# AttoDD.net
KiCad netlist of a schematic drawn in Altium Designer
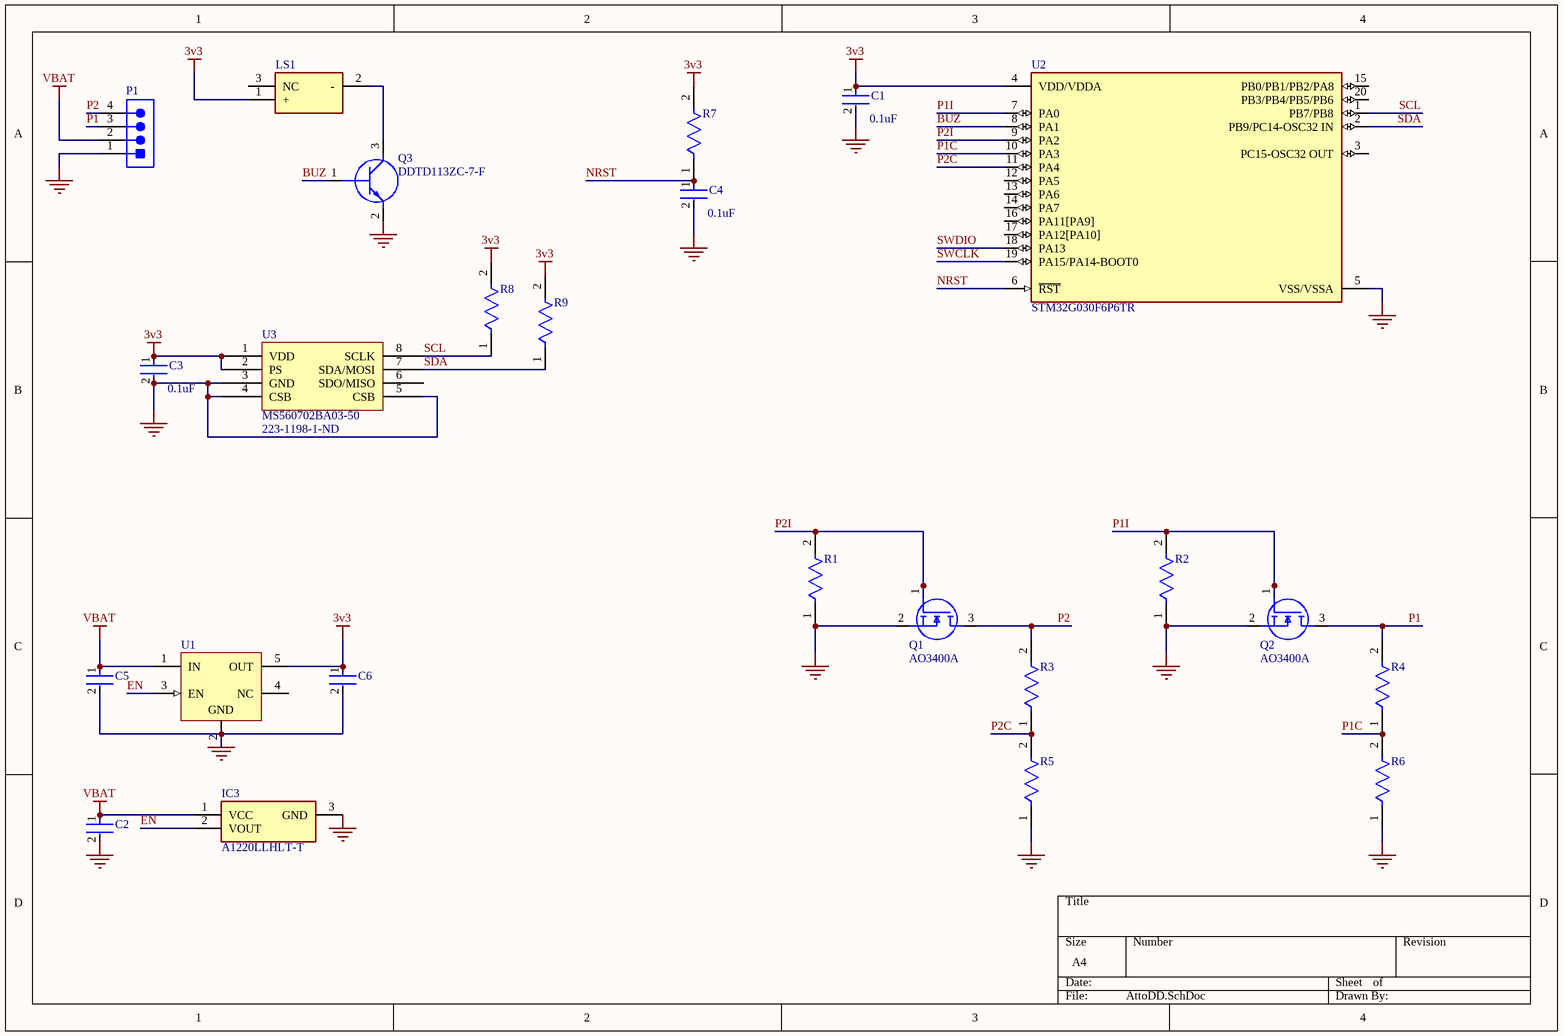
[diagram p0: AttoDD.SchDoc]

(export (version "E")
  (design (tool "Eeschema 10.0.6"))
  (components
    (comp (ref "C1")
      (value "0.1uF")
      (footprint "FP-C0402-BB-MFG")
      (description "CAP CER 0.1UF 10V X5R 0402")
      (fields (field (name "MANUFACTURER") "Kemet") (field (name "TOLERANCE") "0.1"))
      (libsource (lib "Altium Content Vault") (part "b4654b650e69147ec39a6b967a45e02"))
    )
    (comp (ref "C2")
      (value "C0402C105K8PACTU")
      (footprint "FP-C0402C105K8PACTU-MFG")
      (description "CAP CER 1UF 10V X5R 0402")
      (fields (field (name "VOLTAGE") "10V") (field (name "TOLERANCE") "10%"))
      (libsource (lib "Altium Content Vault") (part "11868f565c42a9108669ba33697ecf6"))
    )
    (comp (ref "C3")
      (value "0.1uF")
      (footprint "FP-C0402-BB-MFG")
      (description "CAP CER 0.1UF 10V X5R 0402")
      (fields (field (name "MANUFACTURER") "Kemet") (field (name "TOLERANCE") "0.1"))
      (libsource (lib "Altium Content Vault") (part "b4654b650e69147ec39a6b967a45e02"))
    )
    (comp (ref "C4")
      (value "0.1uF")
      (footprint "FP-C0402-BB-MFG")
      (description "CAP CER 0.1UF 10V X5R 0402")
      (fields (field (name "MANUFACTURER") "Kemet") (field (name "TOLERANCE") "0.1"))
      (libsource (lib "Altium Content Vault") (part "b4654b650e69147ec39a6b967a45e02"))
    )
    (comp (ref "C5")
      (value "C0402C105K8PACTU")
      (footprint "FP-C0402C105K8PACTU-MFG")
      (description "CAP CER 1UF 10V X5R 0402")
      (fields (field (name "VOLTAGE") "10V") (field (name "TOLERANCE") "10%"))
      (libsource (lib "Altium Content Vault") (part "11868f565c42a9108669ba33697ecf6"))
    )
    (comp (ref "C6")
      (value "C0402C105K8PACTU")
      (footprint "FP-C0402C105K8PACTU-MFG")
      (description "CAP CER 1UF 10V X5R 0402")
      (fields (field (name "VOLTAGE") "10V") (field (name "TOLERANCE") "10%"))
      (libsource (lib "Altium Content Vault") (part "11868f565c42a9108669ba33697ecf6"))
    )
    (comp (ref "IC3")
      (value "A1220LLHLT-T")
      (footprint "SamacSys:A3213ELHLTT")
      (description "Integrated Circuit")
      (libsource (lib "*") (part "A1220LLHLT-T"))
    )
    (comp (ref "LS1")
      (value "CMT-0525-75-SMT-TR")
      (footprint "SamacSys:CMT052575SMTTR")
      (description "Loudspeaker or Buzzer")
      (libsource (lib "*") (part "CMT-0525-75-SMT-TR"))
    )
    (comp (ref "P1")
      (value "GRPB041VWVN-RC")
      (footprint "SLIN-GRPB041VWVN-RC_V")
      (fields (field (name "MANUFACTURER") "Sullins"))
      (libsource (lib "Altium Content Vault") (part "CN-1P-M-R4"))
    )
    (comp (ref "Q1")
      (value "AO3400A")
      (footprint "SamacSys:SOT95P280X125-3N")
      (description "MOSFET (N-Channel)")
      (libsource (lib "*") (part "AO3400A"))
    )
    (comp (ref "Q2")
      (value "AO3400A")
      (footprint "SamacSys:SOT95P280X125-3N")
      (description "MOSFET (N-Channel)")
      (libsource (lib "*") (part "AO3400A"))
    )
    (comp (ref "Q3")
      (value "DDTD113ZC-7-F")
      (footprint "SamacSys:SOT96P240X110-3N")
      (description "Transistor BJT NPN")
      (libsource (lib "*") (part "DDTD113ZC-7-F"))
    )
    (comp (ref "R1")
      (value "CRCW0402100KFKED")
      (footprint "FP-CRCW0402-e3-IPC_C")
      (description "RES Thick Film, 100kΩ, 1%, 0.063W, 100ppm/°C, 0402")
      (fields (field (name "TOLERANCE") "1%"))
      (libsource (lib "Altium Content Vault") (part "1029c3af85768c4190bb7ad29bc67b5"))
    )
    (comp (ref "R2")
      (value "CRCW0402100KFKED")
      (footprint "FP-CRCW0402-e3-IPC_C")
      (description "RES Thick Film, 100kΩ, 1%, 0.063W, 100ppm/°C, 0402")
      (fields (field (name "TOLERANCE") "1%"))
      (libsource (lib "Altium Content Vault") (part "1029c3af85768c4190bb7ad29bc67b5"))
    )
    (comp (ref "R3")
      (value "CRCW0402100KFKED")
      (footprint "FP-CRCW0402-e3-IPC_C")
      (description "RES Thick Film, 100kΩ, 1%, 0.063W, 100ppm/°C, 0402")
      (fields (field (name "TOLERANCE") "1%"))
      (libsource (lib "Altium Content Vault") (part "1029c3af85768c4190bb7ad29bc67b5"))
    )
    (comp (ref "R4")
      (value "CRCW0402100KFKED")
      (footprint "FP-CRCW0402-e3-IPC_C")
      (description "RES Thick Film, 100kΩ, 1%, 0.063W, 100ppm/°C, 0402")
      (fields (field (name "TOLERANCE") "1%"))
      (libsource (lib "Altium Content Vault") (part "1029c3af85768c4190bb7ad29bc67b5"))
    )
    (comp (ref "R5")
      (value "CRCW040250K0FKED")
      (footprint "FP-CRCW0402-e3-IPC_A")
      (description "RES Thick Film, 50kΩ, 1%, 0.063W, 100ppm/°C, 0402")
      (fields (field (name "TOLERANCE") "1%"))
      (libsource (lib "Altium Content Vault") (part "1029c3af85768c4190bb7ad29bc67b5"))
    )
    (comp (ref "R6")
      (value "CRCW040250K0FKED")
      (footprint "FP-CRCW0402-e3-IPC_A")
      (description "RES Thick Film, 50kΩ, 1%, 0.063W, 100ppm/°C, 0402")
      (fields (field (name "TOLERANCE") "1%"))
      (libsource (lib "Altium Content Vault") (part "1029c3af85768c4190bb7ad29bc67b5"))
    )
    (comp (ref "R7")
      (value "CRCW040250K0FKED")
      (footprint "FP-CRCW0402-e3-IPC_A")
      (description "RES Thick Film, 50kΩ, 1%, 0.063W, 100ppm/°C, 0402")
      (fields (field (name "TOLERANCE") "1%"))
      (libsource (lib "Altium Content Vault") (part "1029c3af85768c4190bb7ad29bc67b5"))
    )
    (comp (ref "R8")
      (value "RC0402JR-074K7L")
      (footprint "FP-RC0402-0_4-MFG")
      (fields (field (name "TOLERANCE") "5%"))
      (libsource (lib "Altium Content Vault") (part "RC0402JR-074K7L"))
    )
    (comp (ref "R9")
      (value "RC0402JR-074K7L")
      (footprint "FP-RC0402-0_4-MFG")
      (fields (field (name "TOLERANCE") "5%"))
      (libsource (lib "Altium Content Vault") (part "RC0402JR-074K7L"))
    )
    (comp (ref "U1")
      (value "TLV70033DCKR")
      (footprint "DCK0005A_M")
      (fields (field (name "MANUFACTURER") "Texas Instruments"))
      (libsource (lib "Altium Content Vault") (part "TI-TXX7XXXX-5"))
    )
    (comp (ref "U2")
      (value "STM32G030F6P6TR")
      (footprint "FP-TSSOP20-YA-IPC_A")
      (description "IC MCU 32BIT 32KB FLASH 20TSSOP")
      (libsource (lib "Altium Content Vault") (part "be9f3bd3d72e89be6370f9e56c175d8"))
    )
    (comp (ref "U3")
      (value "MS560702BA03-50")
      (footprint "MS5607")
      (description "Barometric Pressure Sensor I2C/SPI")
      (fields
        (field (name "SUPPLIER PART NUMBER 1") "223-1198-1-ND")
        (field (name "MADE BY") "*")
        (field (name "REVIEWED BY") "Adam Rising")
      )
      (libsource (lib "USCRPL") (part "MS560702BA03-50"))
    )
  )
  (nets
    (net (code "1") (name "/BUZ") (class "Default")
      (node (ref "Q3") (pin "1") (pinfunction "B_1") (pintype "passive"))
      (node (ref "U2") (pin "8") (pinfunction "PA1_8") (pintype "bidirectional"))
    )
    (net (code "2") (name "/EN") (class "Default")
      (node (ref "IC3") (pin "2") (pinfunction "VOUT_2") (pintype "passive"))
      (node (ref "U1") (pin "3") (pinfunction "EN_3") (pintype "input"))
    )
    (net (code "3") (name "/NRST") (class "Default")
      (node (ref "C4") (pin "1") (pinfunction "1_1") (pintype "passive"))
      (node (ref "R7") (pin "1") (pinfunction "1_1") (pintype "passive"))
      (node (ref "U2") (pin "6") (pinfunction "~{RST}_6") (pintype "input"))
    )
    (net (code "4") (name "/P1") (class "Default")
      (node (ref "P1") (pin "3") (pinfunction "3_3") (pintype "passive"))
      (node (ref "Q2") (pin "3") (pinfunction "D_3") (pintype "passive"))
      (node (ref "R4") (pin "2") (pinfunction "2_2") (pintype "passive"))
    )
    (net (code "5") (name "/P1C") (class "Default")
      (node (ref "R4") (pin "1") (pinfunction "1_1") (pintype "passive"))
      (node (ref "R6") (pin "2") (pinfunction "2_2") (pintype "passive"))
      (node (ref "U2") (pin "10") (pinfunction "PA3_10") (pintype "bidirectional"))
    )
    (net (code "6") (name "/P1I") (class "Default")
      (node (ref "Q2") (pin "1") (pinfunction "G_1") (pintype "passive"))
      (node (ref "R2") (pin "2") (pinfunction "2_2") (pintype "passive"))
      (node (ref "U2") (pin "7") (pinfunction "PA0_7") (pintype "bidirectional"))
    )
    (net (code "7") (name "/P2") (class "Default")
      (node (ref "P1") (pin "4") (pinfunction "4_4") (pintype "passive"))
      (node (ref "Q1") (pin "3") (pinfunction "D_3") (pintype "passive"))
      (node (ref "R3") (pin "2") (pinfunction "2_2") (pintype "passive"))
    )
    (net (code "8") (name "/P2C") (class "Default")
      (node (ref "R3") (pin "1") (pinfunction "1_1") (pintype "passive"))
      (node (ref "R5") (pin "2") (pinfunction "2_2") (pintype "passive"))
      (node (ref "U2") (pin "11") (pinfunction "PA4_11") (pintype "bidirectional"))
    )
    (net (code "9") (name "/P2I") (class "Default")
      (node (ref "Q1") (pin "1") (pinfunction "G_1") (pintype "passive"))
      (node (ref "R1") (pin "2") (pinfunction "2_2") (pintype "passive"))
      (node (ref "U2") (pin "9") (pinfunction "PA2_9") (pintype "bidirectional"))
    )
    (net (code "10") (name "/SCL") (class "Default")
      (node (ref "R8") (pin "1") (pinfunction "1_1") (pintype "passive"))
      (node (ref "U2") (pin "1") (pinfunction "PB7/PB8_1") (pintype "bidirectional"))
      (node (ref "U3") (pin "8") (pinfunction "SCLK_8") (pintype "passive"))
    )
    (net (code "11") (name "/SDA") (class "Default")
      (node (ref "R9") (pin "1") (pinfunction "1_1") (pintype "passive"))
      (node (ref "U2") (pin "2") (pinfunction "PB9/PC14-OSC32_IN_2") (pintype "bidirectional"))
      (node (ref "U3") (pin "7") (pinfunction "SDA/MOSI_7") (pintype "passive"))
    )
    (net (code "12") (name "/SWCLK") (class "Default")
      (node (ref "U2") (pin "19") (pinfunction "PA15/PA14-BOOT0_19") (pintype "bidirectional"))
    )
    (net (code "13") (name "/SWDIO") (class "Default")
      (node (ref "U2") (pin "18") (pinfunction "PA13_18") (pintype "bidirectional"))
    )
    (net (code "14") (name "3v3") (class "Default")
      (node (ref "C1") (pin "1") (pinfunction "1_1") (pintype "passive"))
      (node (ref "C3") (pin "1") (pinfunction "1_1") (pintype "passive"))
      (node (ref "C6") (pin "1") (pinfunction "1_1") (pintype "passive"))
      (node (ref "LS1") (pin "1") (pinfunction "+_1") (pintype "passive"))
      (node (ref "R7") (pin "2") (pinfunction "2_2") (pintype "passive"))
      (node (ref "R8") (pin "2") (pinfunction "2_2") (pintype "passive"))
      (node (ref "R9") (pin "2") (pinfunction "2_2") (pintype "passive"))
      (node (ref "U1") (pin "5") (pinfunction "OUT_5") (pintype "power_in"))
      (node (ref "U2") (pin "4") (pinfunction "VDD/VDDA_4") (pintype "power_in"))
      (node (ref "U3") (pin "1") (pinfunction "VDD_1") (pintype "passive"))
      (node (ref "U3") (pin "2") (pinfunction "PS_2") (pintype "passive"))
    )
    (net (code "15") (name "GND") (class "Default")
      (node (ref "C1") (pin "2") (pinfunction "2_2") (pintype "passive"))
      (node (ref "C2") (pin "2") (pinfunction "2_2") (pintype "passive"))
      (node (ref "C3") (pin "2") (pinfunction "2_2") (pintype "passive"))
      (node (ref "C4") (pin "2") (pinfunction "2_2") (pintype "passive"))
      (node (ref "C5") (pin "2") (pinfunction "2_2") (pintype "passive"))
      (node (ref "C6") (pin "2") (pinfunction "2_2") (pintype "passive"))
      (node (ref "IC3") (pin "3") (pinfunction "GND_3") (pintype "passive"))
      (node (ref "P1") (pin "1") (pinfunction "1_1") (pintype "passive"))
      (node (ref "Q1") (pin "2") (pinfunction "S_2") (pintype "passive"))
      (node (ref "Q2") (pin "2") (pinfunction "S_2") (pintype "passive"))
      (node (ref "Q3") (pin "2") (pinfunction "E_2") (pintype "passive"))
      (node (ref "R1") (pin "1") (pinfunction "1_1") (pintype "passive"))
      (node (ref "R2") (pin "1") (pinfunction "1_1") (pintype "passive"))
      (node (ref "R5") (pin "1") (pinfunction "1_1") (pintype "passive"))
      (node (ref "R6") (pin "1") (pinfunction "1_1") (pintype "passive"))
      (node (ref "U1") (pin "2") (pinfunction "GND_2") (pintype "power_in"))
      (node (ref "U2") (pin "5") (pinfunction "VSS/VSSA_5") (pintype "power_in"))
      (node (ref "U3") (pin "3") (pinfunction "GND_3") (pintype "passive"))
      (node (ref "U3") (pin "4") (pinfunction "CSB_4") (pintype "passive"))
      (node (ref "U3") (pin "5") (pinfunction "CSB_5") (pintype "passive"))
    )
    (net (code "16") (name "Net-(LS1--)") (class "Default")
      (node (ref "LS1") (pin "2") (pinfunction "-_2") (pintype "passive"))
      (node (ref "Q3") (pin "3") (pinfunction "C_3") (pintype "passive"))
    )
    (net (code "17") (name "VBAT") (class "Default")
      (node (ref "C2") (pin "1") (pinfunction "1_1") (pintype "passive"))
      (node (ref "C5") (pin "1") (pinfunction "1_1") (pintype "passive"))
      (node (ref "IC3") (pin "1") (pinfunction "VCC_1") (pintype "passive"))
      (node (ref "P1") (pin "2") (pinfunction "2_2") (pintype "passive"))
      (node (ref "U1") (pin "1") (pinfunction "IN_1") (pintype "power_in"))
    )
    (net (code "18") (name "unconnected-(LS1-NC-Pad3)") (class "Default")
      (node (ref "LS1") (pin "3") (pinfunction "NC_3") (pintype "passive"))
    )
    (net (code "19") (name "unconnected-(U1-NC-Pad4)") (class "Default")
      (node (ref "U1") (pin "4") (pinfunction "NC_4") (pintype "passive"))
    )
    (net (code "20") (name "unconnected-(U2-PA5-Pad12)") (class "Default")
      (node (ref "U2") (pin "12") (pinfunction "PA5_12") (pintype "bidirectional"))
    )
    (net (code "21") (name "unconnected-(U2-PA6-Pad13)") (class "Default")
      (node (ref "U2") (pin "13") (pinfunction "PA6_13") (pintype "bidirectional"))
    )
    (net (code "22") (name "unconnected-(U2-PA7-Pad14)") (class "Default")
      (node (ref "U2") (pin "14") (pinfunction "PA7_14") (pintype "bidirectional"))
    )
    (net (code "23") (name "unconnected-(U2-PA11[PA9]-Pad16)") (class "Default")
      (node (ref "U2") (pin "16") (pinfunction "PA11[PA9]_16") (pintype "bidirectional"))
    )
    (net (code "24") (name "unconnected-(U2-PA12[PA10]-Pad17)") (class "Default")
      (node (ref "U2") (pin "17") (pinfunction "PA12[PA10]_17") (pintype "bidirectional"))
    )
    (net (code "25") (name "unconnected-(U2-PB0{slash}PB1{slash}PB2{slash}PA8-Pad15)") (class "Default")
      (node (ref "U2") (pin "15") (pinfunction "PB0/PB1/PB2/PA8_15") (pintype "bidirectional"))
    )
    (net (code "26") (name "unconnected-(U2-PB3{slash}PB4{slash}PB5{slash}PB6-Pad20)") (class "Default")
      (node (ref "U2") (pin "20") (pinfunction "PB3/PB4/PB5/PB6_20") (pintype "bidirectional"))
    )
    (net (code "27") (name "unconnected-(U2-PC15-OSC32_OUT-Pad3)") (class "Default")
      (node (ref "U2") (pin "3") (pinfunction "PC15-OSC32_OUT_3") (pintype "bidirectional"))
    )
    (net (code "28") (name "unconnected-(U3-SDO{slash}MISO-Pad6)") (class "Default")
      (node (ref "U3") (pin "6") (pinfunction "SDO/MISO_6") (pintype "passive"))
    )
  )
)
